# MCU.net
KiCad netlist of a schematic drawn in Altium Designer
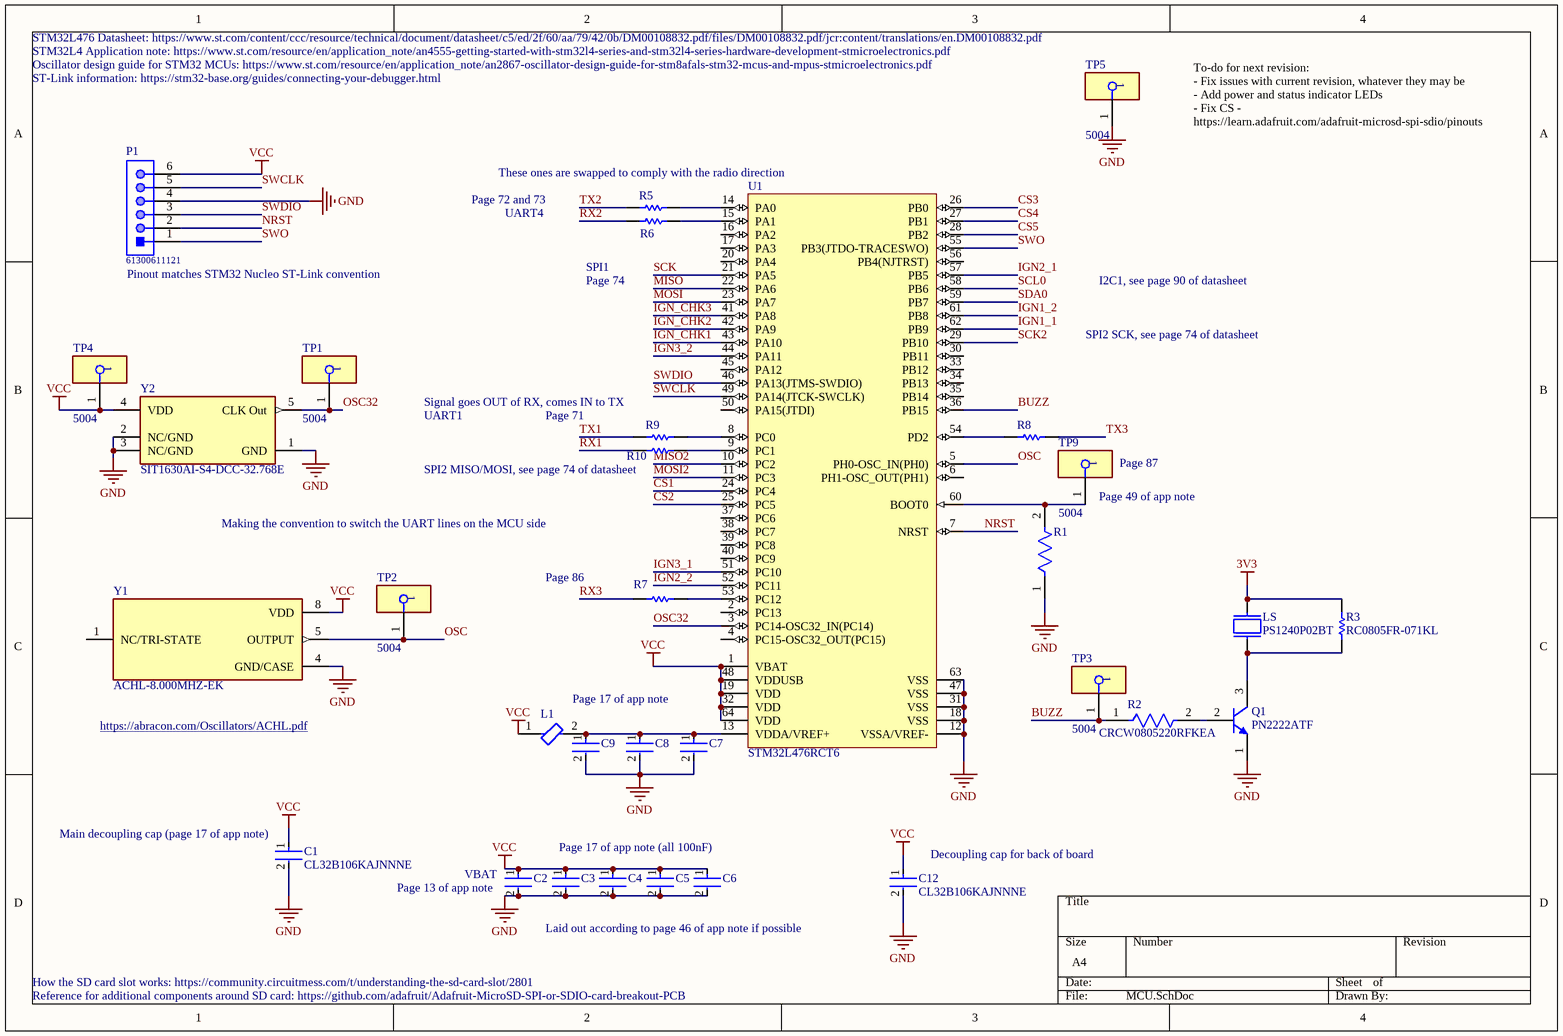
[diagram p0: MCU.SchDoc]

(export (version "E")
  (design (tool "Eeschema 10.0.6"))
  (components
    (comp (ref "C1")
      (value "CL32B106KAJNNNE")
      (footprint "FP-CL32-IPC_B")
      (description "Cap Ceramic 10uF 25V X7R ±10% SMD 1210 +125°C Embossed T/R")
      (fields (field (name "TOLERANCE") "10%") (field (name "VOLTAGE") "25V"))
      (libsource (lib "Altium Content Vault") (part "b4654b650e69147ec39a6b967a45e02"))
    )
    (comp (ref "C2")
      (value "CC0603KRX7R9BB104")
      (footprint "FP-CC0603-DA-MFG")
      (description "CAP CER 0.1UF 50V X7R 0603")
      (fields (field (name "MANUFACTURER") "YAGEO") (field (name "VOLTAGE") "50 V"))
      (libsource (lib "Altium Content Vault") (part "11868f565c42a9108669ba33697ecf6"))
    )
    (comp (ref "C3")
      (value "CC0603KRX7R9BB104")
      (footprint "FP-CC0603-DA-MFG")
      (description "CAP CER 0.1UF 50V X7R 0603")
      (fields (field (name "MANUFACTURER") "YAGEO") (field (name "VOLTAGE") "50 V"))
      (libsource (lib "Altium Content Vault") (part "11868f565c42a9108669ba33697ecf6"))
    )
    (comp (ref "C4")
      (value "CC0603KRX7R9BB104")
      (footprint "FP-CC0603-DA-MFG")
      (description "CAP CER 0.1UF 50V X7R 0603")
      (fields (field (name "MANUFACTURER") "YAGEO") (field (name "VOLTAGE") "50 V"))
      (libsource (lib "Altium Content Vault") (part "11868f565c42a9108669ba33697ecf6"))
    )
    (comp (ref "C5")
      (value "CC0603KRX7R9BB104")
      (footprint "FP-CC0603-DA-MFG")
      (description "CAP CER 0.1UF 50V X7R 0603")
      (fields (field (name "MANUFACTURER") "YAGEO") (field (name "VOLTAGE") "50 V"))
      (libsource (lib "Altium Content Vault") (part "11868f565c42a9108669ba33697ecf6"))
    )
    (comp (ref "C6")
      (value "CC0603KRX7R9BB104")
      (footprint "FP-CC0603-DA-MFG")
      (description "CAP CER 0.1UF 50V X7R 0603")
      (fields (field (name "MANUFACTURER") "YAGEO") (field (name "VOLTAGE") "50 V"))
      (libsource (lib "Altium Content Vault") (part "11868f565c42a9108669ba33697ecf6"))
    )
    (comp (ref "C7")
      (value "CC0603KRX7R9BB104")
      (footprint "FP-CC0603-DA-MFG")
      (description "CAP CER 0.1UF 50V X7R 0603")
      (fields (field (name "MANUFACTURER") "YAGEO") (field (name "VOLTAGE") "50 V"))
      (libsource (lib "Altium Content Vault") (part "11868f565c42a9108669ba33697ecf6"))
    )
    (comp (ref "C8")
      (value "CC0603KRX7R9BB103")
      (footprint "FP-CC0603-DA-MFG")
      (description "CAP CER 10000PF 50V X7R 0603")
      (fields (field (name "TOLERANCE") "0.1") (field (name "MANUFACTURER") "YAGEO"))
      (libsource (lib "Altium Content Vault") (part "11868f565c42a9108669ba33697ecf6"))
    )
    (comp (ref "C9")
      (value "CL10A105KO8NNNC")
      (footprint "FP-CL10-IPC_A")
      (description "Cap Ceramic 1uF 16V X5R ±10% Pad SMD 0603 +85°C T/R")
      (fields (field (name "TOLERANCE") "10%") (field (name "VOLTAGE") "16V"))
      (libsource (lib "Altium Content Vault") (part "b4654b650e69147ec39a6b967a45e02"))
    )
    (comp (ref "C12")
      (value "CL32B106KAJNNNE")
      (footprint "FP-CL32-IPC_B")
      (description "Cap Ceramic 10uF 25V X7R ±10% SMD 1210 +125°C Embossed T/R")
      (fields (field (name "TOLERANCE") "10%") (field (name "VOLTAGE") "25V"))
      (libsource (lib "Altium Content Vault") (part "b4654b650e69147ec39a6b967a45e02"))
    )
    (comp (ref "L1")
      (value "BLM18EG601SN1D")
      (footprint "FP-BLM18-0_15-t0_8-MFG")
      (description "Chip Ferrite Bead, 0603, 600Ω @ 100MHz, 0.35Ω, 25%, 500mA")
      (fields (field (name "TOLERANCE") "25%") (field (name "LCSC PART #") "C20345"))
      (libsource (lib "Altium Content Vault") (part "5f30dd21d616792df468990f7003faa"))
    )
    (comp (ref "LS")
      (value "PS1240P02BT")
      (footprint "XDCR_PS1240P02BT")
      (description "Buzzers Transducer, Externally Driven Piezo 3V 4kHz 60dB @ 3V, 10cm Through Hole PC Pins")
      (fields (field (name "MF") "TDK"))
      (libsource (lib "PS1240P02BT") (part "PS1240P02BT"))
    )
    (comp (ref "P1")
      (value "61300611121")
      (footprint "61300611121")
      (description "THT Vertical Pin Header WR-PHD, Pitch 2.54 mm, Single Row, 6 pins")
      (fields (field (name "MANUFACTURER") "Wurth Elektronik") (field (name "PUBLISHER") "WurthElektronik"))
      (libsource (lib "Altium Content Vault") (part "WE-CN-1P-M-R6"))
    )
    (comp (ref "Q1")
      (value "PN2222ATF")
      (footprint "FAIR-TO-92-3")
      (description "NPN General-Purpose Amplifier, 40 V, -55 to 150 degC, 3-Pin TO-92, RoHS, Tape and Reel")
      (fields (field (name "MANUFACTURER") "FairchildSemiconductor"))
      (libsource (lib "Altium Content Vault") (part "BJT-NPN-EBC-3"))
    )
    (comp (ref "R1")
      (value "AC0805FR-0710KL")
      (footprint "FP-AC0805-MFG")
      (description "RES SMD 10K OHM 1% 1/8W 0805")
      (fields
        (field (name "OCTOPART") "https://octopart.com/ac0805fr-0710kl-yageo-21711112")
        (field (name "MANUFACTURER") "Yageo")
      )
      (libsource (lib "Altium Content Vault") (part "1029c3af85768c4190bb7ad29bc67b5"))
    )
    (comp (ref "R2")
      (value "CRCW0805220RFKEA")
      (footprint "FP-CRCW0805-e3-MFG")
      (description "RES Thick Film, 220Ω, 1%, 0.125W, 100ppm/°C, 0805")
      (fields (field (name "TOLERANCE") "1%") (field (name "LCSC PART #") "C844204"))
      (libsource (lib "Altium Content Vault") (part "1029c3af85768c4190bb7ad29bc67b5"))
    )
    (comp (ref "R3")
      (value "RC0805FR-071KL")
      (footprint "RESC2013X60X35ML10T20")
      (description "Chip Resistor, 1 KOhm, +/- 1%, 125 mW, -55 to 155 degC, 0805 (2012 Metric), RoHS, Tape and Reel")
      (fields (field (name "TOLERANCE") "1%") (field (name "MANUFACTURER") "Yageo"))
      (libsource (lib "Altium Content Vault") (part "RES-2"))
    )
    (comp (ref "R5")
      (value "RC0603JR-070RL")
      (footprint "RESC1608X55X25ML10T15")
      (description "Chip Resistor, 0 Ohm, +/- 5%, 0.1 W, -55 to 155 degC, 0603 (1608 Metric), RoHS, Tape and Reel")
      (fields (field (name "TOLERANCE") "5%") (field (name "MANUFACTURER") "Yageo"))
      (libsource (lib "Altium Content Vault") (part "RES-2"))
    )
    (comp (ref "R6")
      (value "RC0603JR-070RL")
      (footprint "RESC1608X55X25ML10T15")
      (description "Chip Resistor, 0 Ohm, +/- 5%, 0.1 W, -55 to 155 degC, 0603 (1608 Metric), RoHS, Tape and Reel")
      (fields (field (name "TOLERANCE") "5%") (field (name "MANUFACTURER") "Yageo"))
      (libsource (lib "Altium Content Vault") (part "RES-2"))
    )
    (comp (ref "R7")
      (value "RC0603JR-070RL")
      (footprint "RESC1608X55X25ML10T15")
      (description "Chip Resistor, 0 Ohm, +/- 5%, 0.1 W, -55 to 155 degC, 0603 (1608 Metric), RoHS, Tape and Reel")
      (fields (field (name "TOLERANCE") "5%") (field (name "MANUFACTURER") "Yageo"))
      (libsource (lib "Altium Content Vault") (part "RES-2"))
    )
    (comp (ref "R8")
      (value "RC0603JR-070RL")
      (footprint "RESC1608X55X25ML10T15")
      (description "Chip Resistor, 0 Ohm, +/- 5%, 0.1 W, -55 to 155 degC, 0603 (1608 Metric), RoHS, Tape and Reel")
      (fields (field (name "TOLERANCE") "5%") (field (name "MANUFACTURER") "Yageo"))
      (libsource (lib "Altium Content Vault") (part "RES-2"))
    )
    (comp (ref "R9")
      (value "RC0603JR-070RL")
      (footprint "RESC1608X55X25ML10T15")
      (description "Chip Resistor, 0 Ohm, +/- 5%, 0.1 W, -55 to 155 degC, 0603 (1608 Metric), RoHS, Tape and Reel")
      (fields (field (name "TOLERANCE") "5%") (field (name "MANUFACTURER") "Yageo"))
      (libsource (lib "Altium Content Vault") (part "RES-2"))
    )
    (comp (ref "R10")
      (value "RC0603JR-070RL")
      (footprint "RESC1608X55X25ML10T15")
      (description "Chip Resistor, 0 Ohm, +/- 5%, 0.1 W, -55 to 155 degC, 0603 (1608 Metric), RoHS, Tape and Reel")
      (fields (field (name "TOLERANCE") "5%") (field (name "MANUFACTURER") "Yageo"))
      (libsource (lib "Altium Content Vault") (part "RES-2"))
    )
    (comp (ref "TP1")
      (value "5004")
      (footprint "FP-5004-MFG")
      (description "PC TEST POINT MINIATURE YELLOW")
      (fields
        (field (name "MANUFACTURER") "Keystone")
        (field (name "OCTOPART") "https://octopart.com/5004-keystone-28591")
      )
      (libsource (lib "Altium Content Vault") (part "98815daf2f2c152b0c43f5ab9800df6"))
    )
    (comp (ref "TP2")
      (value "5004")
      (footprint "FP-5004-MFG")
      (description "PC TEST POINT MINIATURE YELLOW")
      (fields
        (field (name "MANUFACTURER") "Keystone")
        (field (name "OCTOPART") "https://octopart.com/5004-keystone-28591")
      )
      (libsource (lib "Altium Content Vault") (part "98815daf2f2c152b0c43f5ab9800df6"))
    )
    (comp (ref "TP3")
      (value "5004")
      (footprint "FP-5004-MFG")
      (description "PC TEST POINT MINIATURE YELLOW")
      (fields
        (field (name "MANUFACTURER") "Keystone")
        (field (name "OCTOPART") "https://octopart.com/5004-keystone-28591")
      )
      (libsource (lib "Altium Content Vault") (part "98815daf2f2c152b0c43f5ab9800df6"))
    )
    (comp (ref "TP4")
      (value "5004")
      (footprint "FP-5004-MFG")
      (description "PC TEST POINT MINIATURE YELLOW")
      (fields
        (field (name "MANUFACTURER") "Keystone")
        (field (name "OCTOPART") "https://octopart.com/5004-keystone-28591")
      )
      (libsource (lib "Altium Content Vault") (part "98815daf2f2c152b0c43f5ab9800df6"))
    )
    (comp (ref "TP5")
      (value "5004")
      (footprint "FP-5004-MFG")
      (description "PC TEST POINT MINIATURE YELLOW")
      (fields
        (field (name "MANUFACTURER") "Keystone")
        (field (name "OCTOPART") "https://octopart.com/5004-keystone-28591")
      )
      (libsource (lib "Altium Content Vault") (part "98815daf2f2c152b0c43f5ab9800df6"))
    )
    (comp (ref "TP9")
      (value "5004")
      (footprint "FP-5004-MFG")
      (description "PC TEST POINT MINIATURE YELLOW")
      (fields
        (field (name "MANUFACTURER") "Keystone")
        (field (name "OCTOPART") "https://octopart.com/5004-keystone-28591")
      )
      (libsource (lib "Altium Content Vault") (part "98815daf2f2c152b0c43f5ab9800df6"))
    )
    (comp (ref "U1")
      (value "STM32L476RCT6")
      (footprint "STM-LQFP64_L")
      (fields (field (name "MANUFACTURER") "STMicroelectronics") (field (name "LCSC PART #") "C73245"))
      (libsource (lib "Altium Content Vault") (part "MC-ARM-STM32L4X6-LQFP64"))
    )
    (comp (ref "Y1")
      (value "ACHL-8.000MHZ-EK")
      (footprint "XTAL_ACHL-8.000MHZ-EK")
      (libsource (lib "ACHL-8.000MHZ-EK") (part "ACHL-8.000MHZ-EK"))
    )
    (comp (ref "Y2")
      (value "SIT1630AI-S4-DCC-32.768E")
      (footprint "FP-SiT1630-S-IPC_A")
      (description "MEMS OSC XO 32.7680KHZ LVCMOS")
      (libsource (lib "Altium Content Vault") (part "93232e8e4595095947db9034d0b3f1e"))
    )
  )
  (nets
    (net (code "1") (name "/BUZZ") (class "Default")
      (node (ref "R2") (pin "1") (pinfunction "1_1") (pintype "passive"))
      (node (ref "TP3") (pin "1") (pinfunction "1_1") (pintype "passive"))
      (node (ref "U1") (pin "36") (pinfunction "PB15_36") (pintype "bidirectional"))
    )
    (net (code "2") (name "/CS1") (class "Default")
      (node (ref "U1") (pin "24") (pinfunction "PC4_24") (pintype "bidirectional"))
    )
    (net (code "3") (name "/CS2") (class "Default")
      (node (ref "U1") (pin "25") (pinfunction "PC5_25") (pintype "bidirectional"))
    )
    (net (code "4") (name "/CS3") (class "Default")
      (node (ref "U1") (pin "26") (pinfunction "PB0_26") (pintype "bidirectional"))
    )
    (net (code "5") (name "/CS4") (class "Default")
      (node (ref "U1") (pin "27") (pinfunction "PB1_27") (pintype "bidirectional"))
    )
    (net (code "6") (name "/CS5") (class "Default")
      (node (ref "U1") (pin "28") (pinfunction "PB2_28") (pintype "bidirectional"))
    )
    (net (code "7") (name "/IGN1_1") (class "Default")
      (node (ref "U1") (pin "62") (pinfunction "PB9_62") (pintype "bidirectional"))
    )
    (net (code "8") (name "/IGN1_2") (class "Default")
      (node (ref "U1") (pin "61") (pinfunction "PB8_61") (pintype "bidirectional"))
    )
    (net (code "9") (name "/IGN2_1") (class "Default")
      (node (ref "U1") (pin "57") (pinfunction "PB5_57") (pintype "bidirectional"))
    )
    (net (code "10") (name "/IGN2_2") (class "Default")
      (node (ref "U1") (pin "52") (pinfunction "PC11_52") (pintype "bidirectional"))
    )
    (net (code "11") (name "/IGN3_1") (class "Default")
      (node (ref "U1") (pin "51") (pinfunction "PC10_51") (pintype "bidirectional"))
    )
    (net (code "12") (name "/IGN3_2") (class "Default")
      (node (ref "U1") (pin "44") (pinfunction "PA11_44") (pintype "bidirectional"))
    )
    (net (code "13") (name "/IGN_CHK1") (class "Default")
      (node (ref "U1") (pin "43") (pinfunction "PA10_43") (pintype "bidirectional"))
    )
    (net (code "14") (name "/IGN_CHK2") (class "Default")
      (node (ref "U1") (pin "42") (pinfunction "PA9_42") (pintype "bidirectional"))
    )
    (net (code "15") (name "/IGN_CHK3") (class "Default")
      (node (ref "U1") (pin "41") (pinfunction "PA8_41") (pintype "bidirectional"))
    )
    (net (code "16") (name "/MISO") (class "Default")
      (node (ref "U1") (pin "22") (pinfunction "PA6_22") (pintype "bidirectional"))
    )
    (net (code "17") (name "/MISO2") (class "Default")
      (node (ref "U1") (pin "10") (pinfunction "PC2_10") (pintype "bidirectional"))
    )
    (net (code "18") (name "/MOSI") (class "Default")
      (node (ref "U1") (pin "23") (pinfunction "PA7_23") (pintype "bidirectional"))
    )
    (net (code "19") (name "/MOSI2") (class "Default")
      (node (ref "U1") (pin "11") (pinfunction "PC3_11") (pintype "bidirectional"))
    )
    (net (code "20") (name "/NRST") (class "Default")
      (node (ref "P1") (pin "2") (pinfunction "2_2") (pintype "passive"))
      (node (ref "U1") (pin "7") (pinfunction "NRST_7") (pintype "bidirectional"))
    )
    (net (code "21") (name "/OSC") (class "Default")
      (node (ref "TP2") (pin "1") (pinfunction "1_1") (pintype "passive"))
      (node (ref "U1") (pin "5") (pinfunction "PH0-OSC_IN(PH0)_5") (pintype "bidirectional"))
      (node (ref "Y1") (pin "5") (pinfunction "OUTPUT_5") (pintype "output"))
    )
    (net (code "22") (name "/OSC32") (class "Default")
      (node (ref "TP1") (pin "1") (pinfunction "1_1") (pintype "passive"))
      (node (ref "U1") (pin "3") (pinfunction "PC14-OSC32_IN(PC14)_3") (pintype "bidirectional"))
      (node (ref "Y2") (pin "5") (pinfunction "CLK_Out_5") (pintype "output"))
    )
    (net (code "23") (name "/RX1") (class "Default")
      (node (ref "R10") (pin "1") (pinfunction "1_1") (pintype "passive"))
    )
    (net (code "24") (name "/RX2") (class "Default")
      (node (ref "R6") (pin "1") (pinfunction "1_1") (pintype "passive"))
    )
    (net (code "25") (name "/RX3") (class "Default")
      (node (ref "R7") (pin "1") (pinfunction "1_1") (pintype "passive"))
    )
    (net (code "26") (name "/SCK") (class "Default")
      (node (ref "U1") (pin "21") (pinfunction "PA5_21") (pintype "bidirectional"))
    )
    (net (code "27") (name "/SCK2") (class "Default")
      (node (ref "U1") (pin "29") (pinfunction "PB10_29") (pintype "bidirectional"))
    )
    (net (code "28") (name "/SCL0") (class "Default")
      (node (ref "U1") (pin "58") (pinfunction "PB6_58") (pintype "bidirectional"))
    )
    (net (code "29") (name "/SDA0") (class "Default")
      (node (ref "U1") (pin "59") (pinfunction "PB7_59") (pintype "bidirectional"))
    )
    (net (code "30") (name "/SWCLK") (class "Default")
      (node (ref "P1") (pin "5") (pinfunction "5_5") (pintype "passive"))
      (node (ref "U1") (pin "49") (pinfunction "PA14(JTCK-SWCLK)_49") (pintype "bidirectional"))
    )
    (net (code "31") (name "/SWDIO") (class "Default")
      (node (ref "P1") (pin "3") (pinfunction "3_3") (pintype "passive"))
      (node (ref "U1") (pin "46") (pinfunction "PA13(JTMS-SWDIO)_46") (pintype "bidirectional"))
    )
    (net (code "32") (name "/SWO") (class "Default")
      (node (ref "P1") (pin "1") (pinfunction "1_1") (pintype "passive"))
      (node (ref "U1") (pin "55") (pinfunction "PB3(JTDO-TRACESWO)_55") (pintype "bidirectional"))
    )
    (net (code "33") (name "/TX1") (class "Default")
      (node (ref "R9") (pin "1") (pinfunction "1_1") (pintype "passive"))
    )
    (net (code "34") (name "/TX2") (class "Default")
      (node (ref "R5") (pin "1") (pinfunction "1_1") (pintype "passive"))
    )
    (net (code "35") (name "/TX3") (class "Default")
      (node (ref "R8") (pin "2") (pinfunction "2_2") (pintype "passive"))
    )
    (net (code "36") (name "3V3") (class "Default")
      (node (ref "LS") (pin "2") (pinfunction "2_2") (pintype "passive"))
      (node (ref "R3") (pin "2") (pinfunction "2_2") (pintype "passive"))
    )
    (net (code "37") (name "GND") (class "Default")
      (node (ref "C1") (pin "2") (pinfunction "2_2") (pintype "passive"))
      (node (ref "C12") (pin "2") (pinfunction "2_2") (pintype "passive"))
      (node (ref "C2") (pin "2") (pinfunction "2_2") (pintype "passive"))
      (node (ref "C3") (pin "2") (pinfunction "2_2") (pintype "passive"))
      (node (ref "C4") (pin "2") (pinfunction "2_2") (pintype "passive"))
      (node (ref "C5") (pin "2") (pinfunction "2_2") (pintype "passive"))
      (node (ref "C6") (pin "2") (pinfunction "2_2") (pintype "passive"))
      (node (ref "C7") (pin "2") (pinfunction "2_2") (pintype "passive"))
      (node (ref "C8") (pin "2") (pinfunction "2_2") (pintype "passive"))
      (node (ref "C9") (pin "2") (pinfunction "2_2") (pintype "passive"))
      (node (ref "P1") (pin "4") (pinfunction "4_4") (pintype "passive"))
      (node (ref "Q1") (pin "1") (pinfunction "E_1") (pintype "passive"))
      (node (ref "R1") (pin "1") (pinfunction "1_1") (pintype "passive"))
      (node (ref "TP5") (pin "1") (pinfunction "1_1") (pintype "passive"))
      (node (ref "U1") (pin "12") (pinfunction "VSSA/VREF-_12") (pintype "power_in"))
      (node (ref "U1") (pin "18") (pinfunction "VSS_18") (pintype "power_in"))
      (node (ref "U1") (pin "31") (pinfunction "VSS_31") (pintype "power_in"))
      (node (ref "U1") (pin "47") (pinfunction "VSS_47") (pintype "power_in"))
      (node (ref "U1") (pin "63") (pinfunction "VSS_63") (pintype "power_in"))
      (node (ref "Y1") (pin "4") (pinfunction "GND/CASE_4") (pintype "passive"))
      (node (ref "Y2") (pin "1") (pinfunction "GND_1") (pintype "power_in"))
      (node (ref "Y2") (pin "2") (pinfunction "NC/GND_2") (pintype "power_in"))
      (node (ref "Y2") (pin "3") (pinfunction "NC/GND_3") (pintype "power_in"))
    )
    (net (code "38") (name "Net-(Q1-B)") (class "Default")
      (node (ref "Q1") (pin "2") (pinfunction "B_2") (pintype "passive"))
      (node (ref "R2") (pin "2") (pinfunction "2_2") (pintype "passive"))
    )
    (net (code "39") (name "Net-(Q1-C)") (class "Default")
      (node (ref "LS") (pin "1") (pinfunction "1_1") (pintype "passive"))
      (node (ref "Q1") (pin "3") (pinfunction "C_3") (pintype "passive"))
      (node (ref "R3") (pin "1") (pinfunction "1_1") (pintype "passive"))
    )
    (net (code "40") (name "Net-(U1-BOOT0)") (class "Default")
      (node (ref "R1") (pin "2") (pinfunction "2_2") (pintype "passive"))
      (node (ref "TP9") (pin "1") (pinfunction "1_1") (pintype "passive"))
      (node (ref "U1") (pin "60") (pinfunction "BOOT0_60") (pintype "input"))
    )
    (net (code "41") (name "Net-(U1-PA0)") (class "Default")
      (node (ref "R5") (pin "2") (pinfunction "2_2") (pintype "passive"))
      (node (ref "U1") (pin "14") (pinfunction "PA0_14") (pintype "bidirectional"))
    )
    (net (code "42") (name "Net-(U1-PA1)") (class "Default")
      (node (ref "R6") (pin "2") (pinfunction "2_2") (pintype "passive"))
      (node (ref "U1") (pin "15") (pinfunction "PA1_15") (pintype "bidirectional"))
    )
    (net (code "43") (name "Net-(U1-PC0)") (class "Default")
      (node (ref "R9") (pin "2") (pinfunction "2_2") (pintype "passive"))
      (node (ref "U1") (pin "8") (pinfunction "PC0_8") (pintype "bidirectional"))
    )
    (net (code "44") (name "Net-(U1-PC1)") (class "Default")
      (node (ref "R10") (pin "2") (pinfunction "2_2") (pintype "passive"))
      (node (ref "U1") (pin "9") (pinfunction "PC1_9") (pintype "bidirectional"))
    )
    (net (code "45") (name "Net-(U1-PC12)") (class "Default")
      (node (ref "R7") (pin "2") (pinfunction "2_2") (pintype "passive"))
      (node (ref "U1") (pin "53") (pinfunction "PC12_53") (pintype "bidirectional"))
    )
    (net (code "46") (name "Net-(U1-PD2)") (class "Default")
      (node (ref "R8") (pin "1") (pinfunction "1_1") (pintype "passive"))
      (node (ref "U1") (pin "54") (pinfunction "PD2_54") (pintype "bidirectional"))
    )
    (net (code "47") (name "Net-(U1-VDDA{slash}VREF+)") (class "Default")
      (node (ref "C7") (pin "1") (pinfunction "1_1") (pintype "passive"))
      (node (ref "C8") (pin "1") (pinfunction "1_1") (pintype "passive"))
      (node (ref "C9") (pin "1") (pinfunction "1_1") (pintype "passive"))
      (node (ref "L1") (pin "2") (pinfunction "2_2") (pintype "passive"))
      (node (ref "U1") (pin "13") (pinfunction "VDDA/VREF+_13") (pintype "power_in"))
    )
    (net (code "48") (name "VCC") (class "Default")
      (node (ref "C1") (pin "1") (pinfunction "1_1") (pintype "passive"))
      (node (ref "C12") (pin "1") (pinfunction "1_1") (pintype "passive"))
      (node (ref "C2") (pin "1") (pinfunction "1_1") (pintype "passive"))
      (node (ref "C3") (pin "1") (pinfunction "1_1") (pintype "passive"))
      (node (ref "C4") (pin "1") (pinfunction "1_1") (pintype "passive"))
      (node (ref "C5") (pin "1") (pinfunction "1_1") (pintype "passive"))
      (node (ref "C6") (pin "1") (pinfunction "1_1") (pintype "passive"))
      (node (ref "L1") (pin "1") (pinfunction "1_1") (pintype "passive"))
      (node (ref "P1") (pin "6") (pinfunction "6_6") (pintype "passive"))
      (node (ref "TP4") (pin "1") (pinfunction "1_1") (pintype "passive"))
      (node (ref "U1") (pin "1") (pinfunction "VBAT_1") (pintype "power_in"))
      (node (ref "U1") (pin "19") (pinfunction "VDD_19") (pintype "power_in"))
      (node (ref "U1") (pin "32") (pinfunction "VDD_32") (pintype "power_in"))
      (node (ref "U1") (pin "48") (pinfunction "VDDUSB_48") (pintype "power_in"))
      (node (ref "U1") (pin "64") (pinfunction "VDD_64") (pintype "power_in"))
      (node (ref "Y1") (pin "8") (pinfunction "VDD_8") (pintype "power_in"))
      (node (ref "Y2") (pin "4") (pinfunction "VDD_4") (pintype "power_in"))
    )
    (net (code "49") (name "unconnected-(U1-PA2-Pad16)") (class "Default")
      (node (ref "U1") (pin "16") (pinfunction "PA2_16") (pintype "bidirectional"))
    )
    (net (code "50") (name "unconnected-(U1-PA3-Pad17)") (class "Default")
      (node (ref "U1") (pin "17") (pinfunction "PA3_17") (pintype "bidirectional"))
    )
    (net (code "51") (name "unconnected-(U1-PA4-Pad20)") (class "Default")
      (node (ref "U1") (pin "20") (pinfunction "PA4_20") (pintype "bidirectional"))
    )
    (net (code "52") (name "unconnected-(U1-PA12-Pad45)") (class "Default")
      (node (ref "U1") (pin "45") (pinfunction "PA12_45") (pintype "bidirectional"))
    )
    (net (code "53") (name "unconnected-(U1-PA15(JTDI)-Pad50)") (class "Default")
      (node (ref "U1") (pin "50") (pinfunction "PA15(JTDI)_50") (pintype "bidirectional"))
    )
    (net (code "54") (name "unconnected-(U1-PB4(NJTRST)-Pad56)") (class "Default")
      (node (ref "U1") (pin "56") (pinfunction "PB4(NJTRST)_56") (pintype "bidirectional"))
    )
    (net (code "55") (name "unconnected-(U1-PB11-Pad30)") (class "Default")
      (node (ref "U1") (pin "30") (pinfunction "PB11_30") (pintype "bidirectional"))
    )
    (net (code "56") (name "unconnected-(U1-PB12-Pad33)") (class "Default")
      (node (ref "U1") (pin "33") (pinfunction "PB12_33") (pintype "bidirectional"))
    )
    (net (code "57") (name "unconnected-(U1-PB13-Pad34)") (class "Default")
      (node (ref "U1") (pin "34") (pinfunction "PB13_34") (pintype "bidirectional"))
    )
    (net (code "58") (name "unconnected-(U1-PB14-Pad35)") (class "Default")
      (node (ref "U1") (pin "35") (pinfunction "PB14_35") (pintype "bidirectional"))
    )
    (net (code "59") (name "unconnected-(U1-PC6-Pad37)") (class "Default")
      (node (ref "U1") (pin "37") (pinfunction "PC6_37") (pintype "bidirectional"))
    )
    (net (code "60") (name "unconnected-(U1-PC7-Pad38)") (class "Default")
      (node (ref "U1") (pin "38") (pinfunction "PC7_38") (pintype "bidirectional"))
    )
    (net (code "61") (name "unconnected-(U1-PC8-Pad39)") (class "Default")
      (node (ref "U1") (pin "39") (pinfunction "PC8_39") (pintype "bidirectional"))
    )
    (net (code "62") (name "unconnected-(U1-PC9-Pad40)") (class "Default")
      (node (ref "U1") (pin "40") (pinfunction "PC9_40") (pintype "bidirectional"))
    )
    (net (code "63") (name "unconnected-(U1-PC13-Pad2)") (class "Default")
      (node (ref "U1") (pin "2") (pinfunction "PC13_2") (pintype "bidirectional"))
    )
    (net (code "64") (name "unconnected-(U1-PC15-OSC32_OUT(PC15)-Pad4)") (class "Default")
      (node (ref "U1") (pin "4") (pinfunction "PC15-OSC32_OUT(PC15)_4") (pintype "bidirectional"))
    )
    (net (code "65") (name "unconnected-(U1-PH1-OSC_OUT(PH1)-Pad6)") (class "Default")
      (node (ref "U1") (pin "6") (pinfunction "PH1-OSC_OUT(PH1)_6") (pintype "bidirectional"))
    )
    (net (code "66") (name "unconnected-(Y1-NC{slash}TRI-STATE-Pad1)") (class "Default")
      (node (ref "Y1") (pin "1") (pinfunction "NC/TRI-STATE_1") (pintype "passive"))
    )
  )
)
